# Headphone-Amplifier-ClassAB-alt3.net
KiCad netlist of a schematic drawn in EAGLE
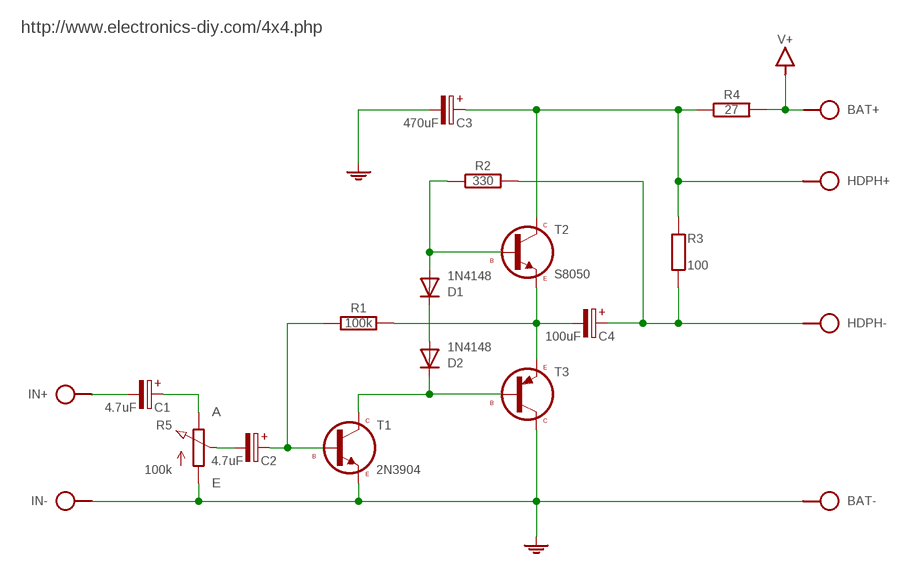
[diagram p0: schematic, sheet 1]

(export (version "E")
  (design (tool "Eeschema 10.0.6"))
  (components
    (comp (ref "BAT")
      (value "SPAD+-+-")
      (footprint "eagle-import:SPAD+-")
      (libsource (lib "eagle-import") (part "SPAD+-+-"))
    )
    (comp (ref "C1")
      (value "4.7uF")
      (footprint "eagle-import:E2,5-3")
      (libsource (lib "eagle-import") (part "CPOL-HE2,5-3"))
    )
    (comp (ref "C2")
      (value "4.7uF")
      (footprint "eagle-import:E2,5-3")
      (libsource (lib "eagle-import") (part "CPOL-HE2,5-3"))
    )
    (comp (ref "C3")
      (value "470uF")
      (footprint "eagle-import:E2,5-5_V")
      (libsource (lib "eagle-import") (part "CPOL-HE2,5-5/V"))
    )
    (comp (ref "C4")
      (value "100uF")
      (footprint "eagle-import:E5-4")
      (libsource (lib "eagle-import") (part "CPOL-HE5-4"))
    )
    (comp (ref "D1")
      (value "1N4148")
      (footprint "eagle-import:DO34-5-V")
      (libsource (lib "eagle-import") (part "DIODE34-5-V"))
    )
    (comp (ref "D2")
      (value "1N4148")
      (footprint "eagle-import:DO34-5V")
      (libsource (lib "eagle-import") (part "DIODE34-5V"))
    )
    (comp (ref "HDPH")
      (value "SPAD+--+")
      (footprint "eagle-import:SPAD-+")
      (libsource (lib "eagle-import") (part "SPAD+--+"))
    )
    (comp (ref "IN")
      (value "SPAD+--+")
      (footprint "eagle-import:SPAD-+")
      (libsource (lib "eagle-import") (part "SPAD+--+"))
    )
    (comp (ref "R1")
      (value "100k")
      (footprint "eagle-import:0204_10")
      (libsource (lib "eagle-import") (part "R-H0204/10"))
    )
    (comp (ref "R2")
      (value "330")
      (footprint "eagle-import:0204_10")
      (libsource (lib "eagle-import") (part "R-H0204/10"))
    )
    (comp (ref "R3")
      (value "100")
      (footprint "eagle-import:0204_10")
      (libsource (lib "eagle-import") (part "R0204/10"))
    )
    (comp (ref "R4")
      (value "27")
      (footprint "eagle-import:0204_10")
      (libsource (lib "eagle-import") (part "R-H0204/10"))
    )
    (comp (ref "R5")
      (value "100k")
      (footprint "eagle-import:CONN-3P")
      (libsource (lib "eagle-import") (part "POT-3P"))
    )
    (comp (ref "T1")
      (value "2N3904")
      (footprint "eagle-import:TO92")
      (libsource (lib "eagle-import") (part "2N3904"))
    )
    (comp (ref "T2")
      (value "S8050")
      (footprint "eagle-import:TO92")
      (libsource (lib "eagle-import") (part "S8050"))
    )
    (comp (ref "T3")
      (value "S8550")
      (footprint "eagle-import:TO92")
      (libsource (lib "eagle-import") (part "S8550"))
    )
  )
  (nets
    (net (code "1") (name "GND") (class "Default")
      (node (ref "BAT") (pin "1") (pinfunction "P$1_1") (pintype "passive"))
      (node (ref "C3") (pin "-") (pinfunction "-_-") (pintype "passive"))
      (node (ref "IN") (pin "1") (pinfunction "P$1_1") (pintype "passive"))
      (node (ref "R5") (pin "1") (pinfunction "A_1") (pintype "passive"))
      (node (ref "T1") (pin "1") (pinfunction "E_1") (pintype "passive"))
      (node (ref "T3") (pin "3") (pinfunction "C_3") (pintype "passive"))
    )
    (net (code "2") (name "Net-(D1-PadC)") (class "Default")
      (node (ref "D1") (pin "C") (pinfunction "C_C") (pintype "passive"))
      (node (ref "D2") (pin "A") (pinfunction "A_A") (pintype "passive"))
    )
    (net (code "3") (name "Net-(HDPHA-P$1)") (class "Default")
      (node (ref "C3") (pin "+") (pinfunction "+_+") (pintype "passive"))
      (node (ref "HDPH") (pin "2") (pinfunction "P$1_2") (pintype "passive"))
      (node (ref "R3") (pin "1") (pinfunction "2_1") (pintype "passive"))
      (node (ref "R4") (pin "1") (pinfunction "1_1") (pintype "passive"))
      (node (ref "T2") (pin "3") (pinfunction "C_3") (pintype "passive"))
    )
    (net (code "4") (name "Net-(HDPHB-P$1)") (class "Default")
      (node (ref "C4") (pin "+") (pinfunction "+_+") (pintype "passive"))
      (node (ref "HDPH") (pin "1") (pinfunction "P$1_1") (pintype "passive"))
      (node (ref "R2") (pin "2") (pinfunction "2_2") (pintype "passive"))
      (node (ref "R3") (pin "2") (pinfunction "1_2") (pintype "passive"))
    )
    (net (code "5") (name "Net-(INA-P$1)") (class "Default")
      (node (ref "C1") (pin "-") (pinfunction "-_-") (pintype "passive"))
      (node (ref "IN") (pin "2") (pinfunction "P$1_2") (pintype "passive"))
    )
    (net (code "6") (name "Net-(R5-E)") (class "Default")
      (node (ref "C1") (pin "+") (pinfunction "+_+") (pintype "passive"))
      (node (ref "R5") (pin "3") (pinfunction "E_3") (pintype "passive"))
    )
    (net (code "7") (name "Net-(R5-S)") (class "Default")
      (node (ref "C2") (pin "-") (pinfunction "-_-") (pintype "passive"))
      (node (ref "R5") (pin "2") (pinfunction "S_2") (pintype "passive"))
    )
    (net (code "8") (name "Net-(T1-B)") (class "Default")
      (node (ref "C2") (pin "+") (pinfunction "+_+") (pintype "passive"))
      (node (ref "R1") (pin "1") (pinfunction "1_1") (pintype "passive"))
      (node (ref "T1") (pin "2") (pinfunction "B_2") (pintype "passive"))
    )
    (net (code "9") (name "Net-(T1-C)") (class "Default")
      (node (ref "D2") (pin "C") (pinfunction "C_C") (pintype "passive"))
      (node (ref "T1") (pin "3") (pinfunction "C_3") (pintype "passive"))
      (node (ref "T3") (pin "2") (pinfunction "B_2") (pintype "passive"))
    )
    (net (code "10") (name "Net-(T2-B)") (class "Default")
      (node (ref "D1") (pin "A") (pinfunction "A_A") (pintype "passive"))
      (node (ref "R2") (pin "1") (pinfunction "1_1") (pintype "passive"))
      (node (ref "T2") (pin "2") (pinfunction "B_2") (pintype "passive"))
    )
    (net (code "11") (name "Net-(T2-E)") (class "Default")
      (node (ref "C4") (pin "-") (pinfunction "-_-") (pintype "passive"))
      (node (ref "R1") (pin "2") (pinfunction "2_2") (pintype "passive"))
      (node (ref "T2") (pin "1") (pinfunction "E_1") (pintype "passive"))
      (node (ref "T3") (pin "1") (pinfunction "E_1") (pintype "passive"))
    )
    (net (code "12") (name "V+") (class "Default")
      (node (ref "BAT") (pin "2") (pinfunction "P$1_2") (pintype "passive"))
      (node (ref "R4") (pin "2") (pinfunction "2_2") (pintype "passive"))
    )
  )
)
